# BMS_AFE_-_Connectors.net
KiCad netlist of a schematic drawn in Altium Designer
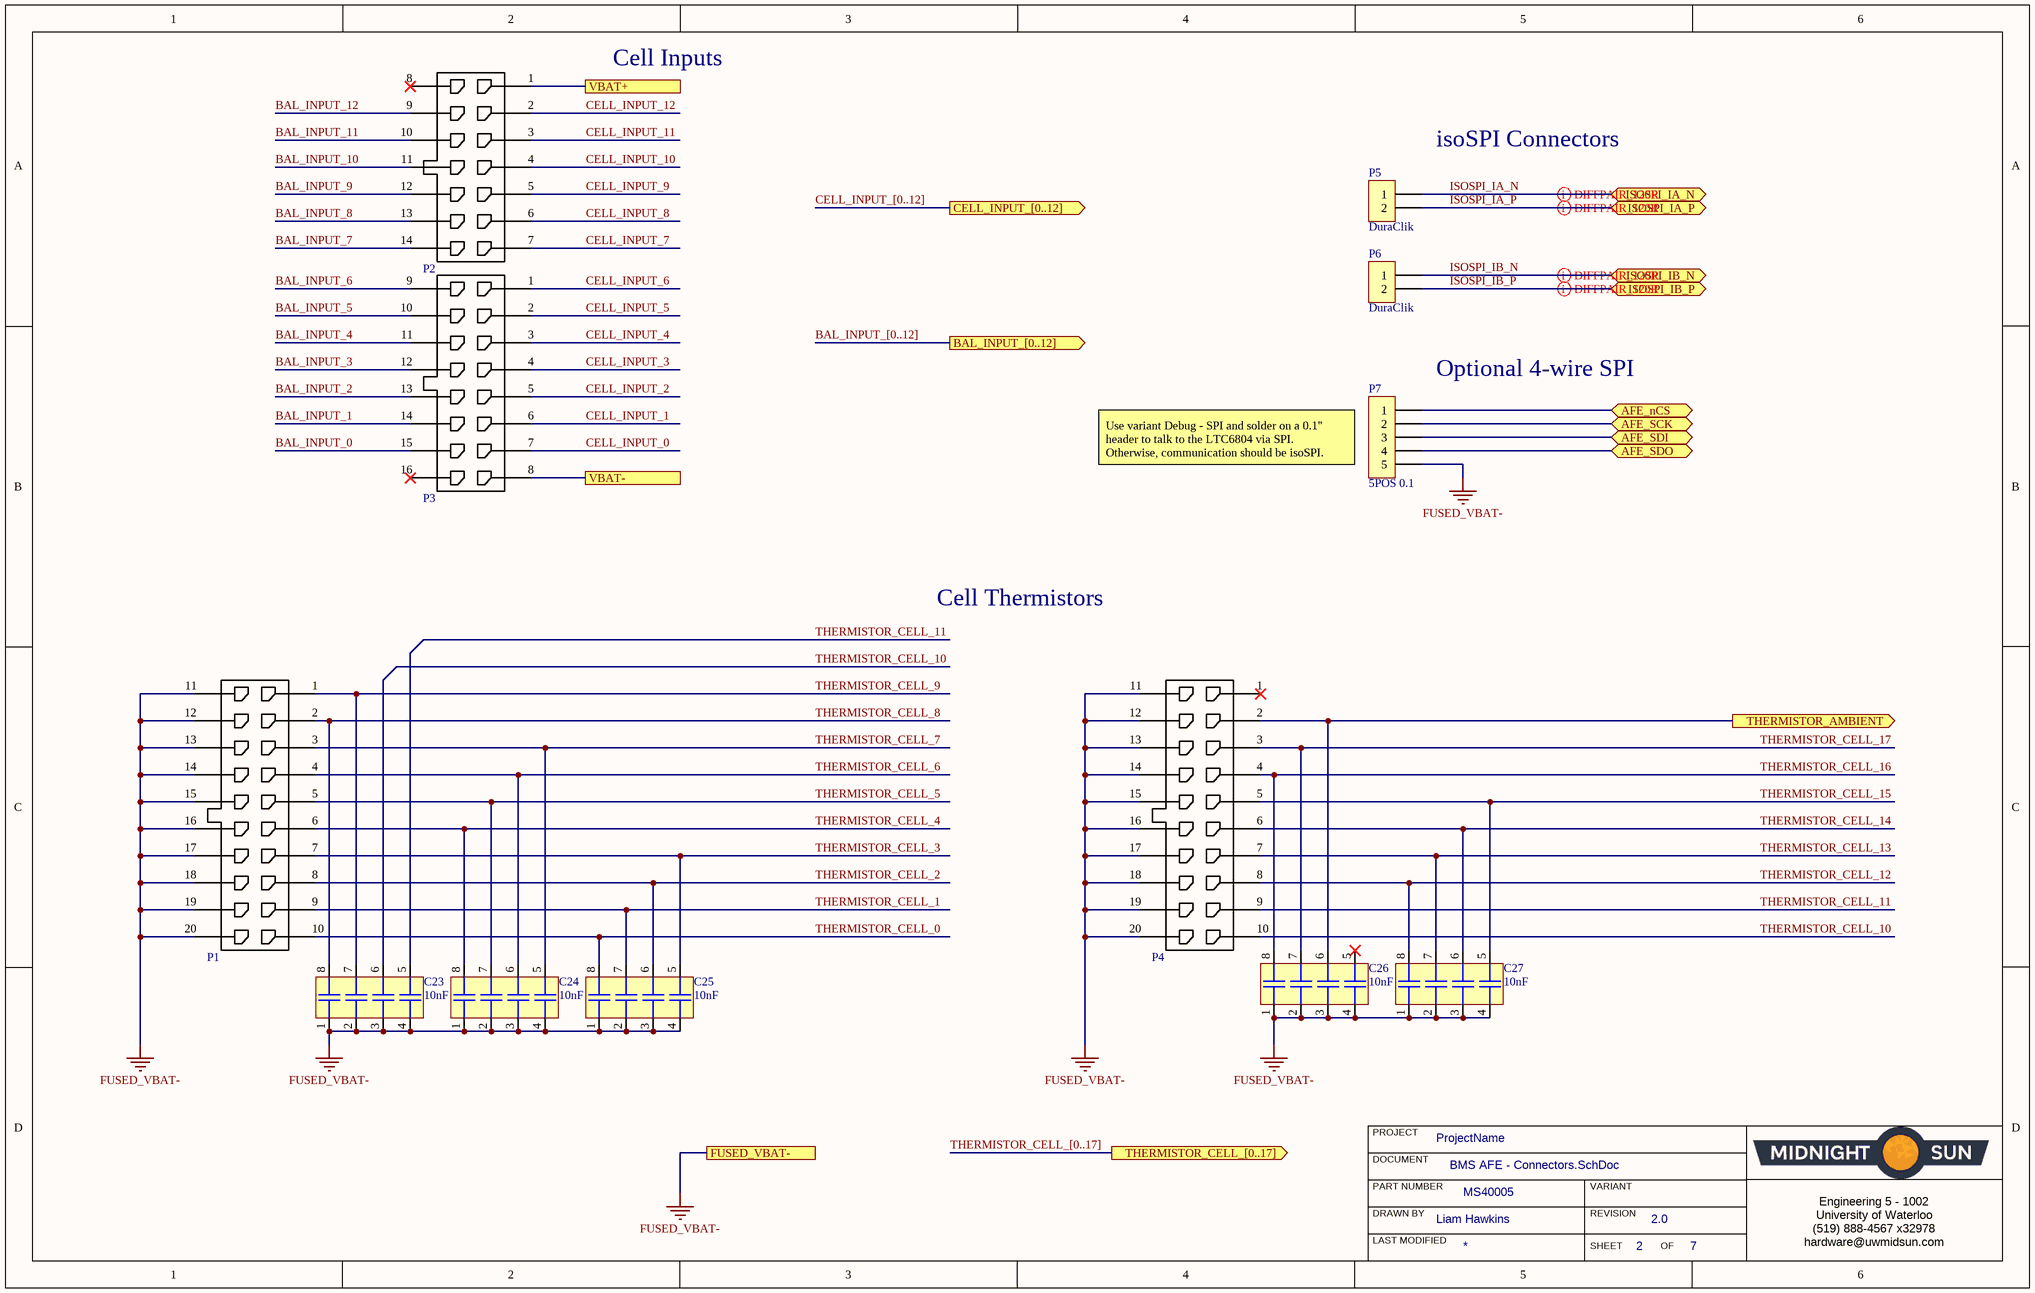
[diagram p0: BMS AFE - Connectors.SchDoc]

(export (version "E")
  (design (tool "Eeschema 10.0.6"))
  (components
    (comp (ref "C23")
      (value "CAP ARRAY 10000PF 50V X7R 0612")
      (footprint "CAP ARRAY 4 POS 0612")
      (description "10000pF Isolated Capacitor  Array 50V X7R 0612 (1632 Metric)")
      (fields
        (field (name "CAPACITANCE") "10nF")
        (field (name "TOLERANCE") "10%")
        (field (name "MANUFACTURER") "Yageo")
      )
      (libsource (lib "Schematic Diagrams") (part "CAP ARRAY 10000PF 50V X7R 0612"))
    )
    (comp (ref "C24")
      (value "CAP ARRAY 10000PF 50V X7R 0612")
      (footprint "CAP ARRAY 4 POS 0612")
      (description "10000pF Isolated Capacitor  Array 50V X7R 0612 (1632 Metric)")
      (fields
        (field (name "CAPACITANCE") "10nF")
        (field (name "TOLERANCE") "10%")
        (field (name "MANUFACTURER") "Yageo")
      )
      (libsource (lib "Schematic Diagrams") (part "CAP ARRAY 10000PF 50V X7R 0612"))
    )
    (comp (ref "C25")
      (value "CAP ARRAY 10000PF 50V X7R 0612")
      (footprint "CAP ARRAY 4 POS 0612")
      (description "10000pF Isolated Capacitor  Array 50V X7R 0612 (1632 Metric)")
      (fields
        (field (name "CAPACITANCE") "10nF")
        (field (name "TOLERANCE") "10%")
        (field (name "MANUFACTURER") "Yageo")
      )
      (libsource (lib "Schematic Diagrams") (part "CAP ARRAY 10000PF 50V X7R 0612"))
    )
    (comp (ref "C26")
      (value "CAP ARRAY 10000PF 50V X7R 0612")
      (footprint "CAP ARRAY 4 POS 0612")
      (description "10000pF Isolated Capacitor  Array 50V X7R 0612 (1632 Metric)")
      (fields
        (field (name "CAPACITANCE") "10nF")
        (field (name "TOLERANCE") "10%")
        (field (name "MANUFACTURER") "Yageo")
      )
      (libsource (lib "Schematic Diagrams") (part "CAP ARRAY 10000PF 50V X7R 0612"))
    )
    (comp (ref "C27")
      (value "CAP ARRAY 10000PF 50V X7R 0612")
      (footprint "CAP ARRAY 4 POS 0612")
      (description "10000pF Isolated Capacitor  Array 50V X7R 0612 (1632 Metric)")
      (fields
        (field (name "CAPACITANCE") "10nF")
        (field (name "TOLERANCE") "10%")
        (field (name "MANUFACTURER") "Yageo")
      )
      (libsource (lib "Schematic Diagrams") (part "CAP ARRAY 10000PF 50V X7R 0612"))
    )
    (comp (ref "P1")
      (value "CONN R/A 20POS 3MM")
      (footprint "CONN, R/A 20POS MICRO-FIT 3mm")
      (description "Connector Header Through Hole, Right Angle 20 position 0.118\" (3.00mm)")
      (fields (field (name "MANUFACTURER") "Molex") (field (name "MANUFACTURER PART NUMBER") "0430452021"))
      (libsource (lib "Schematic Diagrams") (part "CONN R/A 20POS 3MM"))
    )
    (comp (ref "P2")
      (value "CONN R/A 14POS 3MM")
      (footprint "CONN, R/A 14POS MICRO-FIT 3mm")
      (description "Connector Header Through Hole, Right Angle 14 position 0.118\" (3.00mm)")
      (fields (field (name "MANUFACTURER") "Molex") (field (name "MANUFACTURER PART NUMBER") "0430451421"))
      (libsource (lib "Schematic Diagrams") (part "CONN R/A 14POS 3MM"))
    )
    (comp (ref "P3")
      (value "CONN R/A 16POS 3MM")
      (footprint "CONN, R/A 16POS MICRO-FIT 3mm")
      (description "Connector Header Through Hole, Right Angle 16 position 0.118\" (3.00mm)")
      (fields (field (name "MANUFACTURER PART NUMBER") "0430451621") (field (name "MANUFACTURER") "Molex"))
      (libsource (lib "Schematic Diagrams") (part "CONN R/A 16POS 3MM"))
    )
    (comp (ref "P4")
      (value "CONN R/A 20POS 3MM")
      (footprint "CONN, R/A 20POS MICRO-FIT 3mm")
      (description "Connector Header Through Hole, Right Angle 20 position 0.118\" (3.00mm)")
      (fields (field (name "MANUFACTURER") "Molex") (field (name "MANUFACTURER PART NUMBER") "0430452021"))
      (libsource (lib "Schematic Diagrams") (part "CONN R/A 20POS 3MM"))
    )
    (comp (ref "P5")
      (value "CONN 2POS DURA-CLIK 0.079\"")
      (footprint "CONN, 2POS Dura-Click")
      (description "2 Positions Header, Shrouded Connector 0.079\" (2.00mm) Surface Mount, Right Angle Tin")
      (fields (field (name "SERIES") "DuraClik"))
      (libsource (lib "Schematic Diagrams") (part "CONN 2POS DURA-CLIK 0.079{dblquote}"))
    )
    (comp (ref "P6")
      (value "CONN 2POS DURA-CLIK 0.079\"")
      (footprint "CONN, 2POS Dura-Click")
      (description "2 Positions Header, Shrouded Connector 0.079\" (2.00mm) Surface Mount, Right Angle Tin")
      (fields (field (name "SERIES") "DuraClik"))
      (libsource (lib "Schematic Diagrams") (part "CONN 2POS DURA-CLIK 0.079{dblquote}"))
    )
    (comp (ref "P7")
      (value "5POS 0.1")
      (footprint "CONN, 5POS HEADR 0.1\"")
      (description "5 Positions Header, Breakaway Connector 0.100\" (2.54mm) Through Hole Tin")
      (libsource (lib "Schematic Diagrams") (part "CONN 5POS HEADR MALE 0.1in"))
    )
  )
  (nets
    (net (code "1") (name "/AFE_SCK") (class "Default")
      (node (ref "P7") (pin "2") (pinfunction "2_2") (pintype "passive"))
    )
    (net (code "2") (name "/AFE_SDI") (class "Default")
      (node (ref "P7") (pin "3") (pinfunction "3_3") (pintype "passive"))
    )
    (net (code "3") (name "/AFE_SDO") (class "Default")
      (node (ref "P7") (pin "4") (pinfunction "4_4") (pintype "passive"))
    )
    (net (code "4") (name "/AFE_nCS") (class "Default")
      (node (ref "P7") (pin "1") (pinfunction "1_1") (pintype "passive"))
    )
    (net (code "5") (name "/BAL_INPUT_0") (class "Default")
      (node (ref "P3") (pin "15") (pinfunction "15_15") (pintype "passive"))
    )
    (net (code "6") (name "/BAL_INPUT_1") (class "Default")
      (node (ref "P3") (pin "14") (pinfunction "14_14") (pintype "passive"))
    )
    (net (code "7") (name "/BAL_INPUT_2") (class "Default")
      (node (ref "P3") (pin "13") (pinfunction "13_13") (pintype "passive"))
    )
    (net (code "8") (name "/BAL_INPUT_3") (class "Default")
      (node (ref "P3") (pin "12") (pinfunction "12_12") (pintype "passive"))
    )
    (net (code "9") (name "/BAL_INPUT_4") (class "Default")
      (node (ref "P3") (pin "11") (pinfunction "11_11") (pintype "passive"))
    )
    (net (code "10") (name "/BAL_INPUT_5") (class "Default")
      (node (ref "P3") (pin "10") (pinfunction "10_10") (pintype "passive"))
    )
    (net (code "11") (name "/BAL_INPUT_6") (class "Default")
      (node (ref "P3") (pin "9") (pinfunction "9_9") (pintype "passive"))
    )
    (net (code "12") (name "/BAL_INPUT_7") (class "Default")
      (node (ref "P2") (pin "14") (pinfunction "14_14") (pintype "passive"))
    )
    (net (code "13") (name "/BAL_INPUT_8") (class "Default")
      (node (ref "P2") (pin "13") (pinfunction "13_13") (pintype "passive"))
    )
    (net (code "14") (name "/BAL_INPUT_9") (class "Default")
      (node (ref "P2") (pin "12") (pinfunction "12_12") (pintype "passive"))
    )
    (net (code "15") (name "/BAL_INPUT_10") (class "Default")
      (node (ref "P2") (pin "11") (pinfunction "11_11") (pintype "passive"))
    )
    (net (code "16") (name "/BAL_INPUT_11") (class "Default")
      (node (ref "P2") (pin "10") (pinfunction "10_10") (pintype "passive"))
    )
    (net (code "17") (name "/BAL_INPUT_12") (class "Default")
      (node (ref "P2") (pin "9") (pinfunction "9_9") (pintype "passive"))
    )
    (net (code "19") (name "/CELL_INPUT_0") (class "Default")
      (node (ref "P3") (pin "7") (pinfunction "7_7") (pintype "passive"))
    )
    (net (code "20") (name "/CELL_INPUT_1") (class "Default")
      (node (ref "P3") (pin "6") (pinfunction "6_6") (pintype "passive"))
    )
    (net (code "21") (name "/CELL_INPUT_2") (class "Default")
      (node (ref "P3") (pin "5") (pinfunction "5_5") (pintype "passive"))
    )
    (net (code "22") (name "/CELL_INPUT_3") (class "Default")
      (node (ref "P3") (pin "4") (pinfunction "4_4") (pintype "passive"))
    )
    (net (code "23") (name "/CELL_INPUT_4") (class "Default")
      (node (ref "P3") (pin "3") (pinfunction "3_3") (pintype "passive"))
    )
    (net (code "24") (name "/CELL_INPUT_5") (class "Default")
      (node (ref "P3") (pin "2") (pinfunction "2_2") (pintype "passive"))
    )
    (net (code "25") (name "/CELL_INPUT_6") (class "Default")
      (node (ref "P3") (pin "1") (pinfunction "1_1") (pintype "passive"))
    )
    (net (code "26") (name "/CELL_INPUT_7") (class "Default")
      (node (ref "P2") (pin "7") (pinfunction "7_7") (pintype "passive"))
    )
    (net (code "27") (name "/CELL_INPUT_8") (class "Default")
      (node (ref "P2") (pin "6") (pinfunction "6_6") (pintype "passive"))
    )
    (net (code "28") (name "/CELL_INPUT_9") (class "Default")
      (node (ref "P2") (pin "5") (pinfunction "5_5") (pintype "passive"))
    )
    (net (code "29") (name "/CELL_INPUT_10") (class "Default")
      (node (ref "P2") (pin "4") (pinfunction "4_4") (pintype "passive"))
    )
    (net (code "30") (name "/CELL_INPUT_11") (class "Default")
      (node (ref "P2") (pin "3") (pinfunction "3_3") (pintype "passive"))
    )
    (net (code "31") (name "/CELL_INPUT_12") (class "Default")
      (node (ref "P2") (pin "2") (pinfunction "2_2") (pintype "passive"))
    )
    (net (code "33") (name "/ISOSPI_IA_N") (class "Default")
      (node (ref "P5") (pin "1") (pinfunction "1_1") (pintype "passive"))
    )
    (net (code "34") (name "/ISOSPI_IA_P") (class "Default")
      (node (ref "P5") (pin "2") (pinfunction "2_2") (pintype "passive"))
    )
    (net (code "35") (name "/ISOSPI_IB_N") (class "Default")
      (node (ref "P6") (pin "1") (pinfunction "1_1") (pintype "passive"))
    )
    (net (code "36") (name "/ISOSPI_IB_P") (class "Default")
      (node (ref "P6") (pin "2") (pinfunction "2_2") (pintype "passive"))
    )
    (net (code "37") (name "/THERMISTOR_AMBIENT") (class "Default")
      (node (ref "C26") (pin "6") (pinfunction "6_6") (pintype "passive"))
      (node (ref "P4") (pin "2") (pinfunction "2_2") (pintype "passive"))
    )
    (net (code "38") (name "/THERMISTOR_CELL_0") (class "Default")
      (node (ref "C25") (pin "8") (pinfunction "8_8") (pintype "passive"))
      (node (ref "P1") (pin "10") (pinfunction "10_10") (pintype "passive"))
    )
    (net (code "39") (name "/THERMISTOR_CELL_1") (class "Default")
      (node (ref "C25") (pin "7") (pinfunction "7_7") (pintype "passive"))
      (node (ref "P1") (pin "9") (pinfunction "9_9") (pintype "passive"))
    )
    (net (code "40") (name "/THERMISTOR_CELL_2") (class "Default")
      (node (ref "C25") (pin "6") (pinfunction "6_6") (pintype "passive"))
      (node (ref "P1") (pin "8") (pinfunction "8_8") (pintype "passive"))
    )
    (net (code "41") (name "/THERMISTOR_CELL_3") (class "Default")
      (node (ref "C25") (pin "5") (pinfunction "5_5") (pintype "passive"))
      (node (ref "P1") (pin "7") (pinfunction "7_7") (pintype "passive"))
    )
    (net (code "42") (name "/THERMISTOR_CELL_4") (class "Default")
      (node (ref "C24") (pin "8") (pinfunction "8_8") (pintype "passive"))
      (node (ref "P1") (pin "6") (pinfunction "6_6") (pintype "passive"))
    )
    (net (code "43") (name "/THERMISTOR_CELL_5") (class "Default")
      (node (ref "C24") (pin "7") (pinfunction "7_7") (pintype "passive"))
      (node (ref "P1") (pin "5") (pinfunction "5_5") (pintype "passive"))
    )
    (net (code "44") (name "/THERMISTOR_CELL_6") (class "Default")
      (node (ref "C24") (pin "6") (pinfunction "6_6") (pintype "passive"))
      (node (ref "P1") (pin "4") (pinfunction "4_4") (pintype "passive"))
    )
    (net (code "45") (name "/THERMISTOR_CELL_7") (class "Default")
      (node (ref "C24") (pin "5") (pinfunction "5_5") (pintype "passive"))
      (node (ref "P1") (pin "3") (pinfunction "3_3") (pintype "passive"))
    )
    (net (code "46") (name "/THERMISTOR_CELL_8") (class "Default")
      (node (ref "C23") (pin "8") (pinfunction "8_8") (pintype "passive"))
      (node (ref "P1") (pin "2") (pinfunction "2_2") (pintype "passive"))
    )
    (net (code "47") (name "/THERMISTOR_CELL_9") (class "Default")
      (node (ref "C23") (pin "7") (pinfunction "7_7") (pintype "passive"))
      (node (ref "P1") (pin "1") (pinfunction "1_1") (pintype "passive"))
    )
    (net (code "48") (name "/THERMISTOR_CELL_10") (class "Default")
      (node (ref "C23") (pin "6") (pinfunction "6_6") (pintype "passive"))
      (node (ref "P4") (pin "10") (pinfunction "10_10") (pintype "passive"))
    )
    (net (code "49") (name "/THERMISTOR_CELL_11") (class "Default")
      (node (ref "C23") (pin "5") (pinfunction "5_5") (pintype "passive"))
      (node (ref "P4") (pin "9") (pinfunction "9_9") (pintype "passive"))
    )
    (net (code "50") (name "/THERMISTOR_CELL_12") (class "Default")
      (node (ref "C27") (pin "8") (pinfunction "8_8") (pintype "passive"))
      (node (ref "P4") (pin "8") (pinfunction "8_8") (pintype "passive"))
    )
    (net (code "51") (name "/THERMISTOR_CELL_13") (class "Default")
      (node (ref "C27") (pin "7") (pinfunction "7_7") (pintype "passive"))
      (node (ref "P4") (pin "7") (pinfunction "7_7") (pintype "passive"))
    )
    (net (code "52") (name "/THERMISTOR_CELL_14") (class "Default")
      (node (ref "C27") (pin "6") (pinfunction "6_6") (pintype "passive"))
      (node (ref "P4") (pin "6") (pinfunction "6_6") (pintype "passive"))
    )
    (net (code "53") (name "/THERMISTOR_CELL_15") (class "Default")
      (node (ref "C27") (pin "5") (pinfunction "5_5") (pintype "passive"))
      (node (ref "P4") (pin "5") (pinfunction "5_5") (pintype "passive"))
    )
    (net (code "54") (name "/THERMISTOR_CELL_16") (class "Default")
      (node (ref "C26") (pin "8") (pinfunction "8_8") (pintype "passive"))
      (node (ref "P4") (pin "4") (pinfunction "4_4") (pintype "passive"))
    )
    (net (code "55") (name "/THERMISTOR_CELL_17") (class "Default")
      (node (ref "C26") (pin "7") (pinfunction "7_7") (pintype "passive"))
      (node (ref "P4") (pin "3") (pinfunction "3_3") (pintype "passive"))
    )
    (net (code "57") (name "/VBAT+") (class "Default")
      (node (ref "P2") (pin "1") (pinfunction "1_1") (pintype "passive"))
    )
    (net (code "58") (name "/VBAT-") (class "Default")
      (node (ref "P3") (pin "8") (pinfunction "8_8") (pintype "passive"))
    )
    (net (code "59") (name "FUSED_VBAT-") (class "Default")
      (node (ref "C23") (pin "1") (pinfunction "1_1") (pintype "passive"))
      (node (ref "C23") (pin "2") (pinfunction "2_2") (pintype "passive"))
      (node (ref "C23") (pin "3") (pinfunction "3_3") (pintype "passive"))
      (node (ref "C23") (pin "4") (pinfunction "4_4") (pintype "passive"))
      (node (ref "C24") (pin "1") (pinfunction "1_1") (pintype "passive"))
      (node (ref "C24") (pin "2") (pinfunction "2_2") (pintype "passive"))
      (node (ref "C24") (pin "3") (pinfunction "3_3") (pintype "passive"))
      (node (ref "C24") (pin "4") (pinfunction "4_4") (pintype "passive"))
      (node (ref "C25") (pin "1") (pinfunction "1_1") (pintype "passive"))
      (node (ref "C25") (pin "2") (pinfunction "2_2") (pintype "passive"))
      (node (ref "C25") (pin "3") (pinfunction "3_3") (pintype "passive"))
      (node (ref "C25") (pin "4") (pinfunction "4_4") (pintype "passive"))
      (node (ref "C26") (pin "1") (pinfunction "1_1") (pintype "passive"))
      (node (ref "C26") (pin "2") (pinfunction "2_2") (pintype "passive"))
      (node (ref "C26") (pin "3") (pinfunction "3_3") (pintype "passive"))
      (node (ref "C26") (pin "4") (pinfunction "4_4") (pintype "passive"))
      (node (ref "C27") (pin "1") (pinfunction "1_1") (pintype "passive"))
      (node (ref "C27") (pin "2") (pinfunction "2_2") (pintype "passive"))
      (node (ref "C27") (pin "3") (pinfunction "3_3") (pintype "passive"))
      (node (ref "C27") (pin "4") (pinfunction "4_4") (pintype "passive"))
      (node (ref "P1") (pin "11") (pinfunction "11_11") (pintype "passive"))
      (node (ref "P1") (pin "12") (pinfunction "12_12") (pintype "passive"))
      (node (ref "P1") (pin "13") (pinfunction "13_13") (pintype "passive"))
      (node (ref "P1") (pin "14") (pinfunction "14_14") (pintype "passive"))
      (node (ref "P1") (pin "15") (pinfunction "15_15") (pintype "passive"))
      (node (ref "P1") (pin "16") (pinfunction "16_16") (pintype "passive"))
      (node (ref "P1") (pin "17") (pinfunction "17_17") (pintype "passive"))
      (node (ref "P1") (pin "18") (pinfunction "18_18") (pintype "passive"))
      (node (ref "P1") (pin "19") (pinfunction "19_19") (pintype "passive"))
      (node (ref "P1") (pin "20") (pinfunction "20_20") (pintype "passive"))
      (node (ref "P4") (pin "11") (pinfunction "11_11") (pintype "passive"))
      (node (ref "P4") (pin "12") (pinfunction "12_12") (pintype "passive"))
      (node (ref "P4") (pin "13") (pinfunction "13_13") (pintype "passive"))
      (node (ref "P4") (pin "14") (pinfunction "14_14") (pintype "passive"))
      (node (ref "P4") (pin "15") (pinfunction "15_15") (pintype "passive"))
      (node (ref "P4") (pin "16") (pinfunction "16_16") (pintype "passive"))
      (node (ref "P4") (pin "17") (pinfunction "17_17") (pintype "passive"))
      (node (ref "P4") (pin "18") (pinfunction "18_18") (pintype "passive"))
      (node (ref "P4") (pin "19") (pinfunction "19_19") (pintype "passive"))
      (node (ref "P4") (pin "20") (pinfunction "20_20") (pintype "passive"))
      (node (ref "P7") (pin "5") (pinfunction "5_5") (pintype "passive"))
    )
    (net (code "60") (name "unconnected-(C26-Pad5)") (class "Default")
      (node (ref "C26") (pin "5") (pinfunction "5_5") (pintype "passive+no_connect"))
    )
    (net (code "61") (name "unconnected-(P2-Pad8)") (class "Default")
      (node (ref "P2") (pin "8") (pinfunction "8_8") (pintype "passive+no_connect"))
    )
    (net (code "62") (name "unconnected-(P3-Pad16)") (class "Default")
      (node (ref "P3") (pin "16") (pinfunction "16_16") (pintype "passive+no_connect"))
    )
    (net (code "63") (name "unconnected-(P4-Pad1)") (class "Default")
      (node (ref "P4") (pin "1") (pinfunction "1_1") (pintype "passive+no_connect"))
    )
  )
)
